# MasterCtrl_v1_0_4.net
KiCad netlist of a schematic drawn in EasyEDA Pro
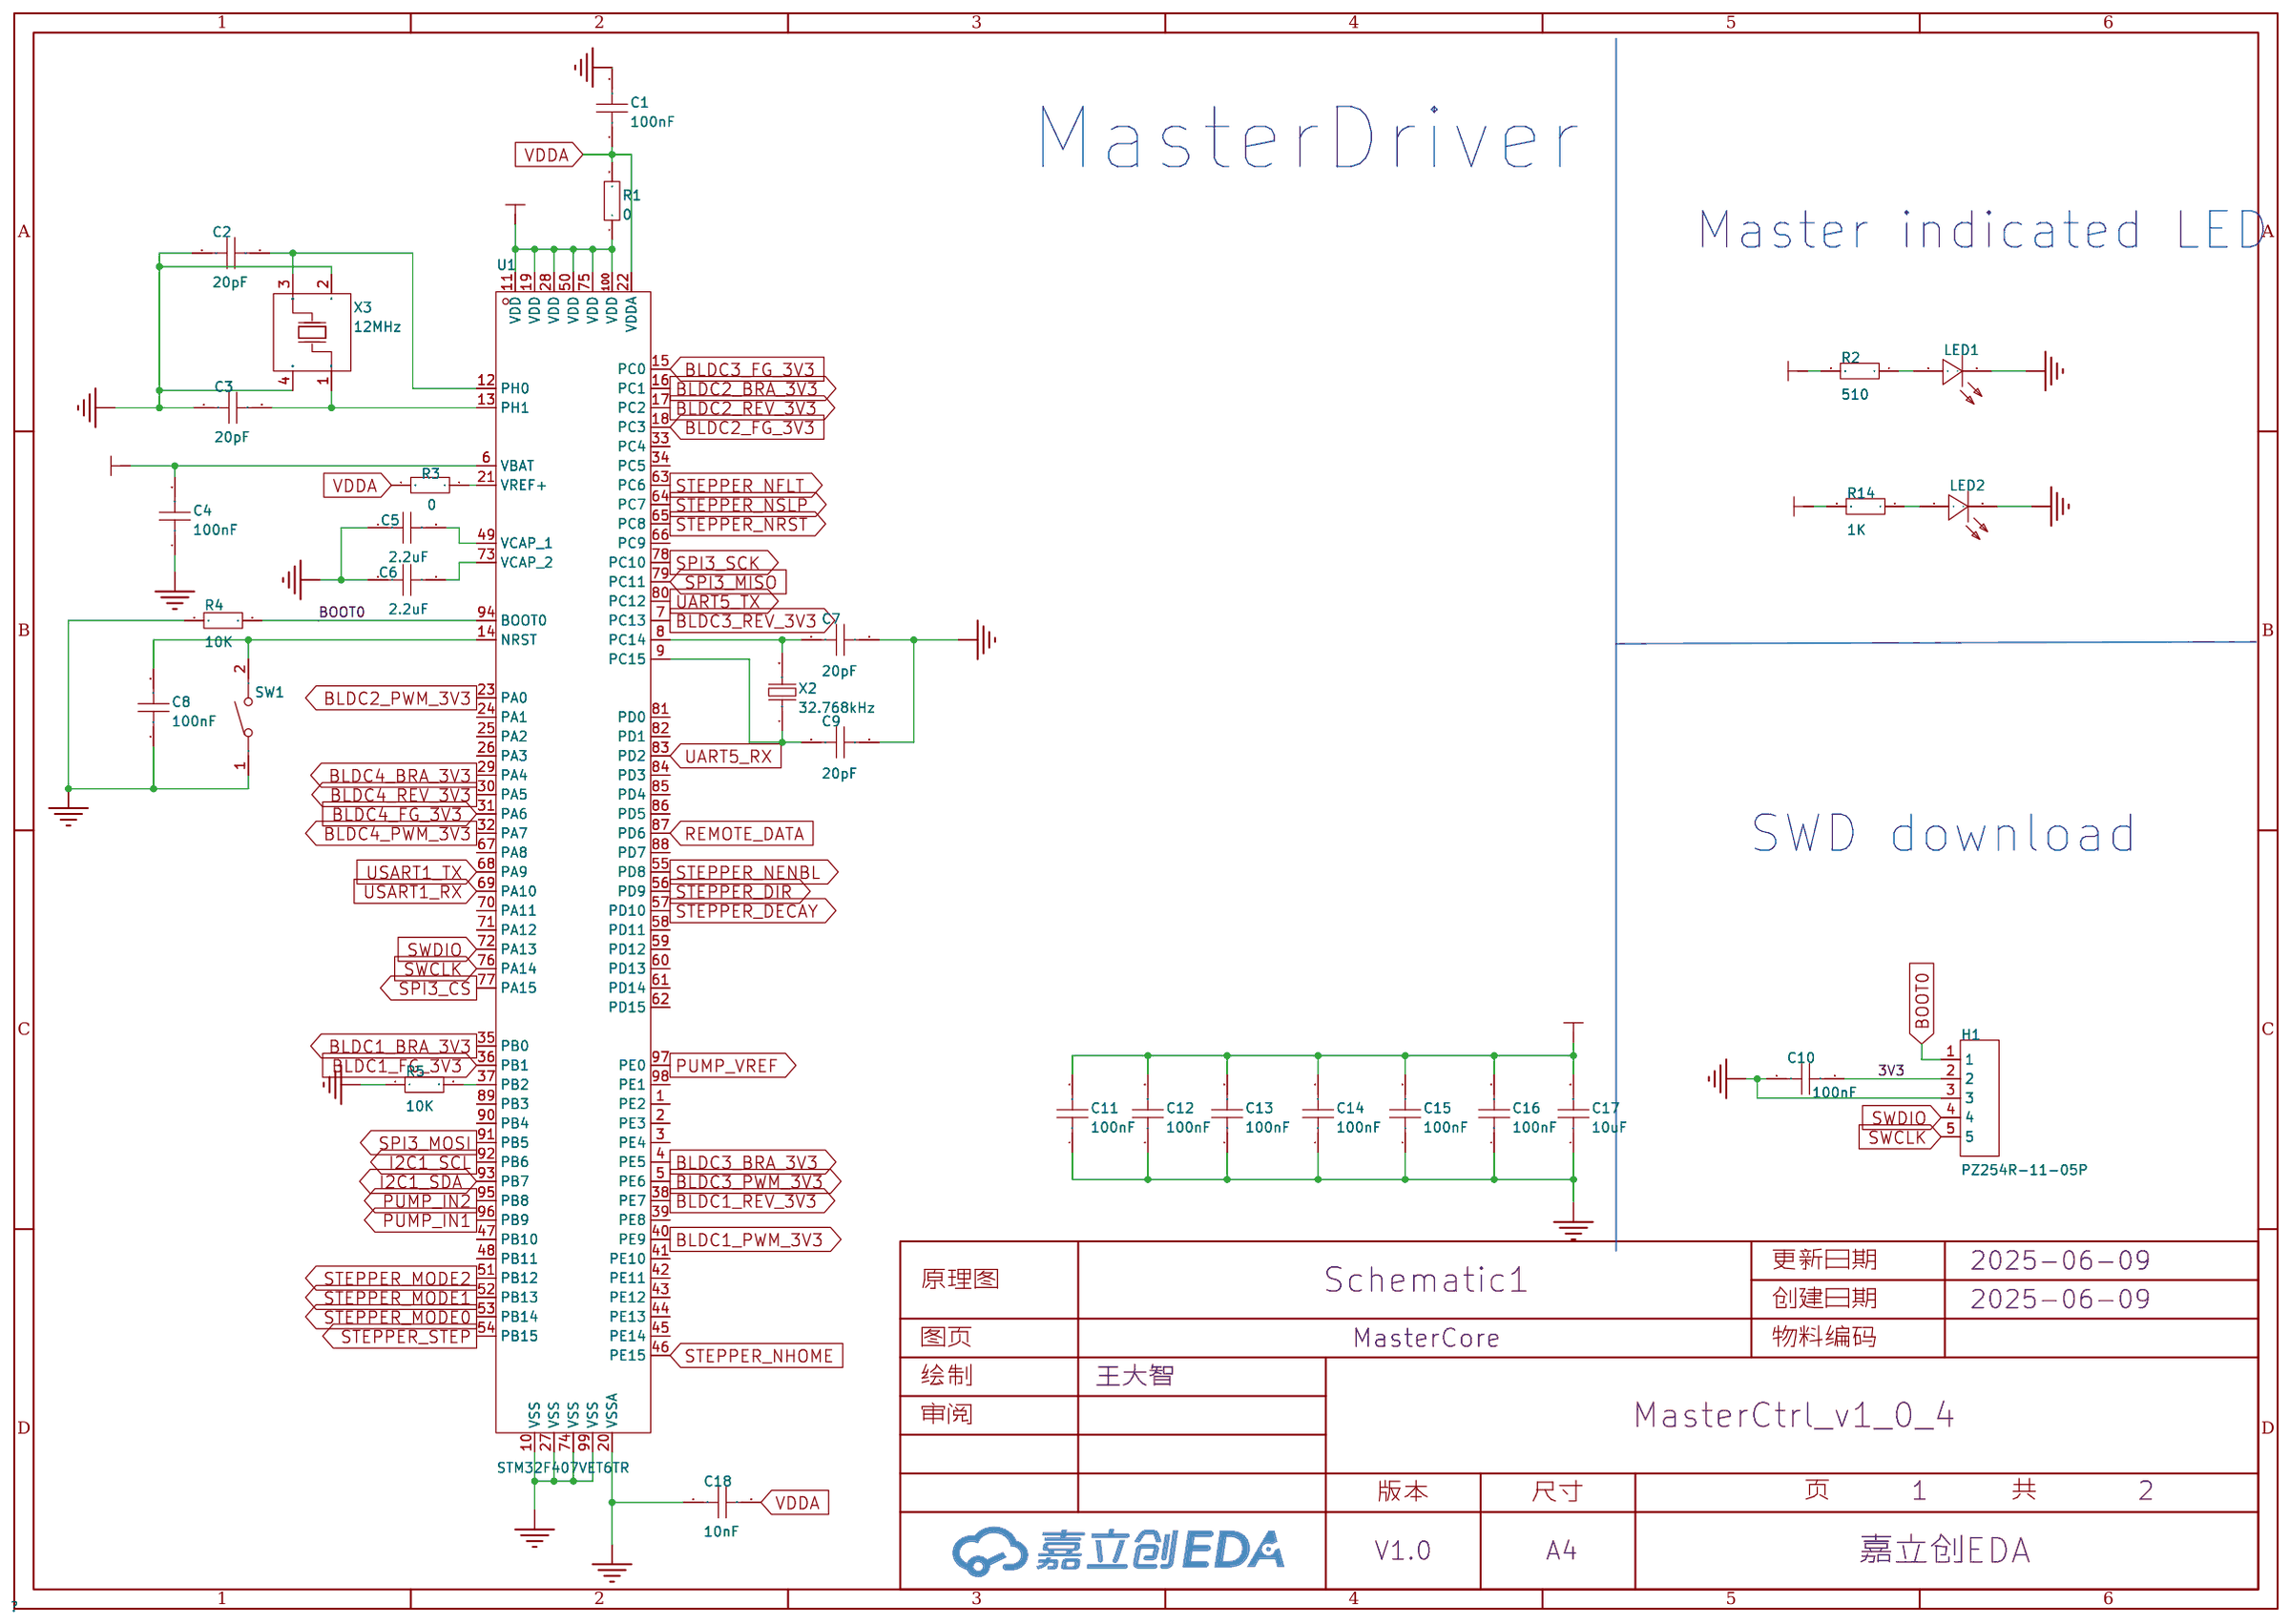
[diagram p0: MasterCore]
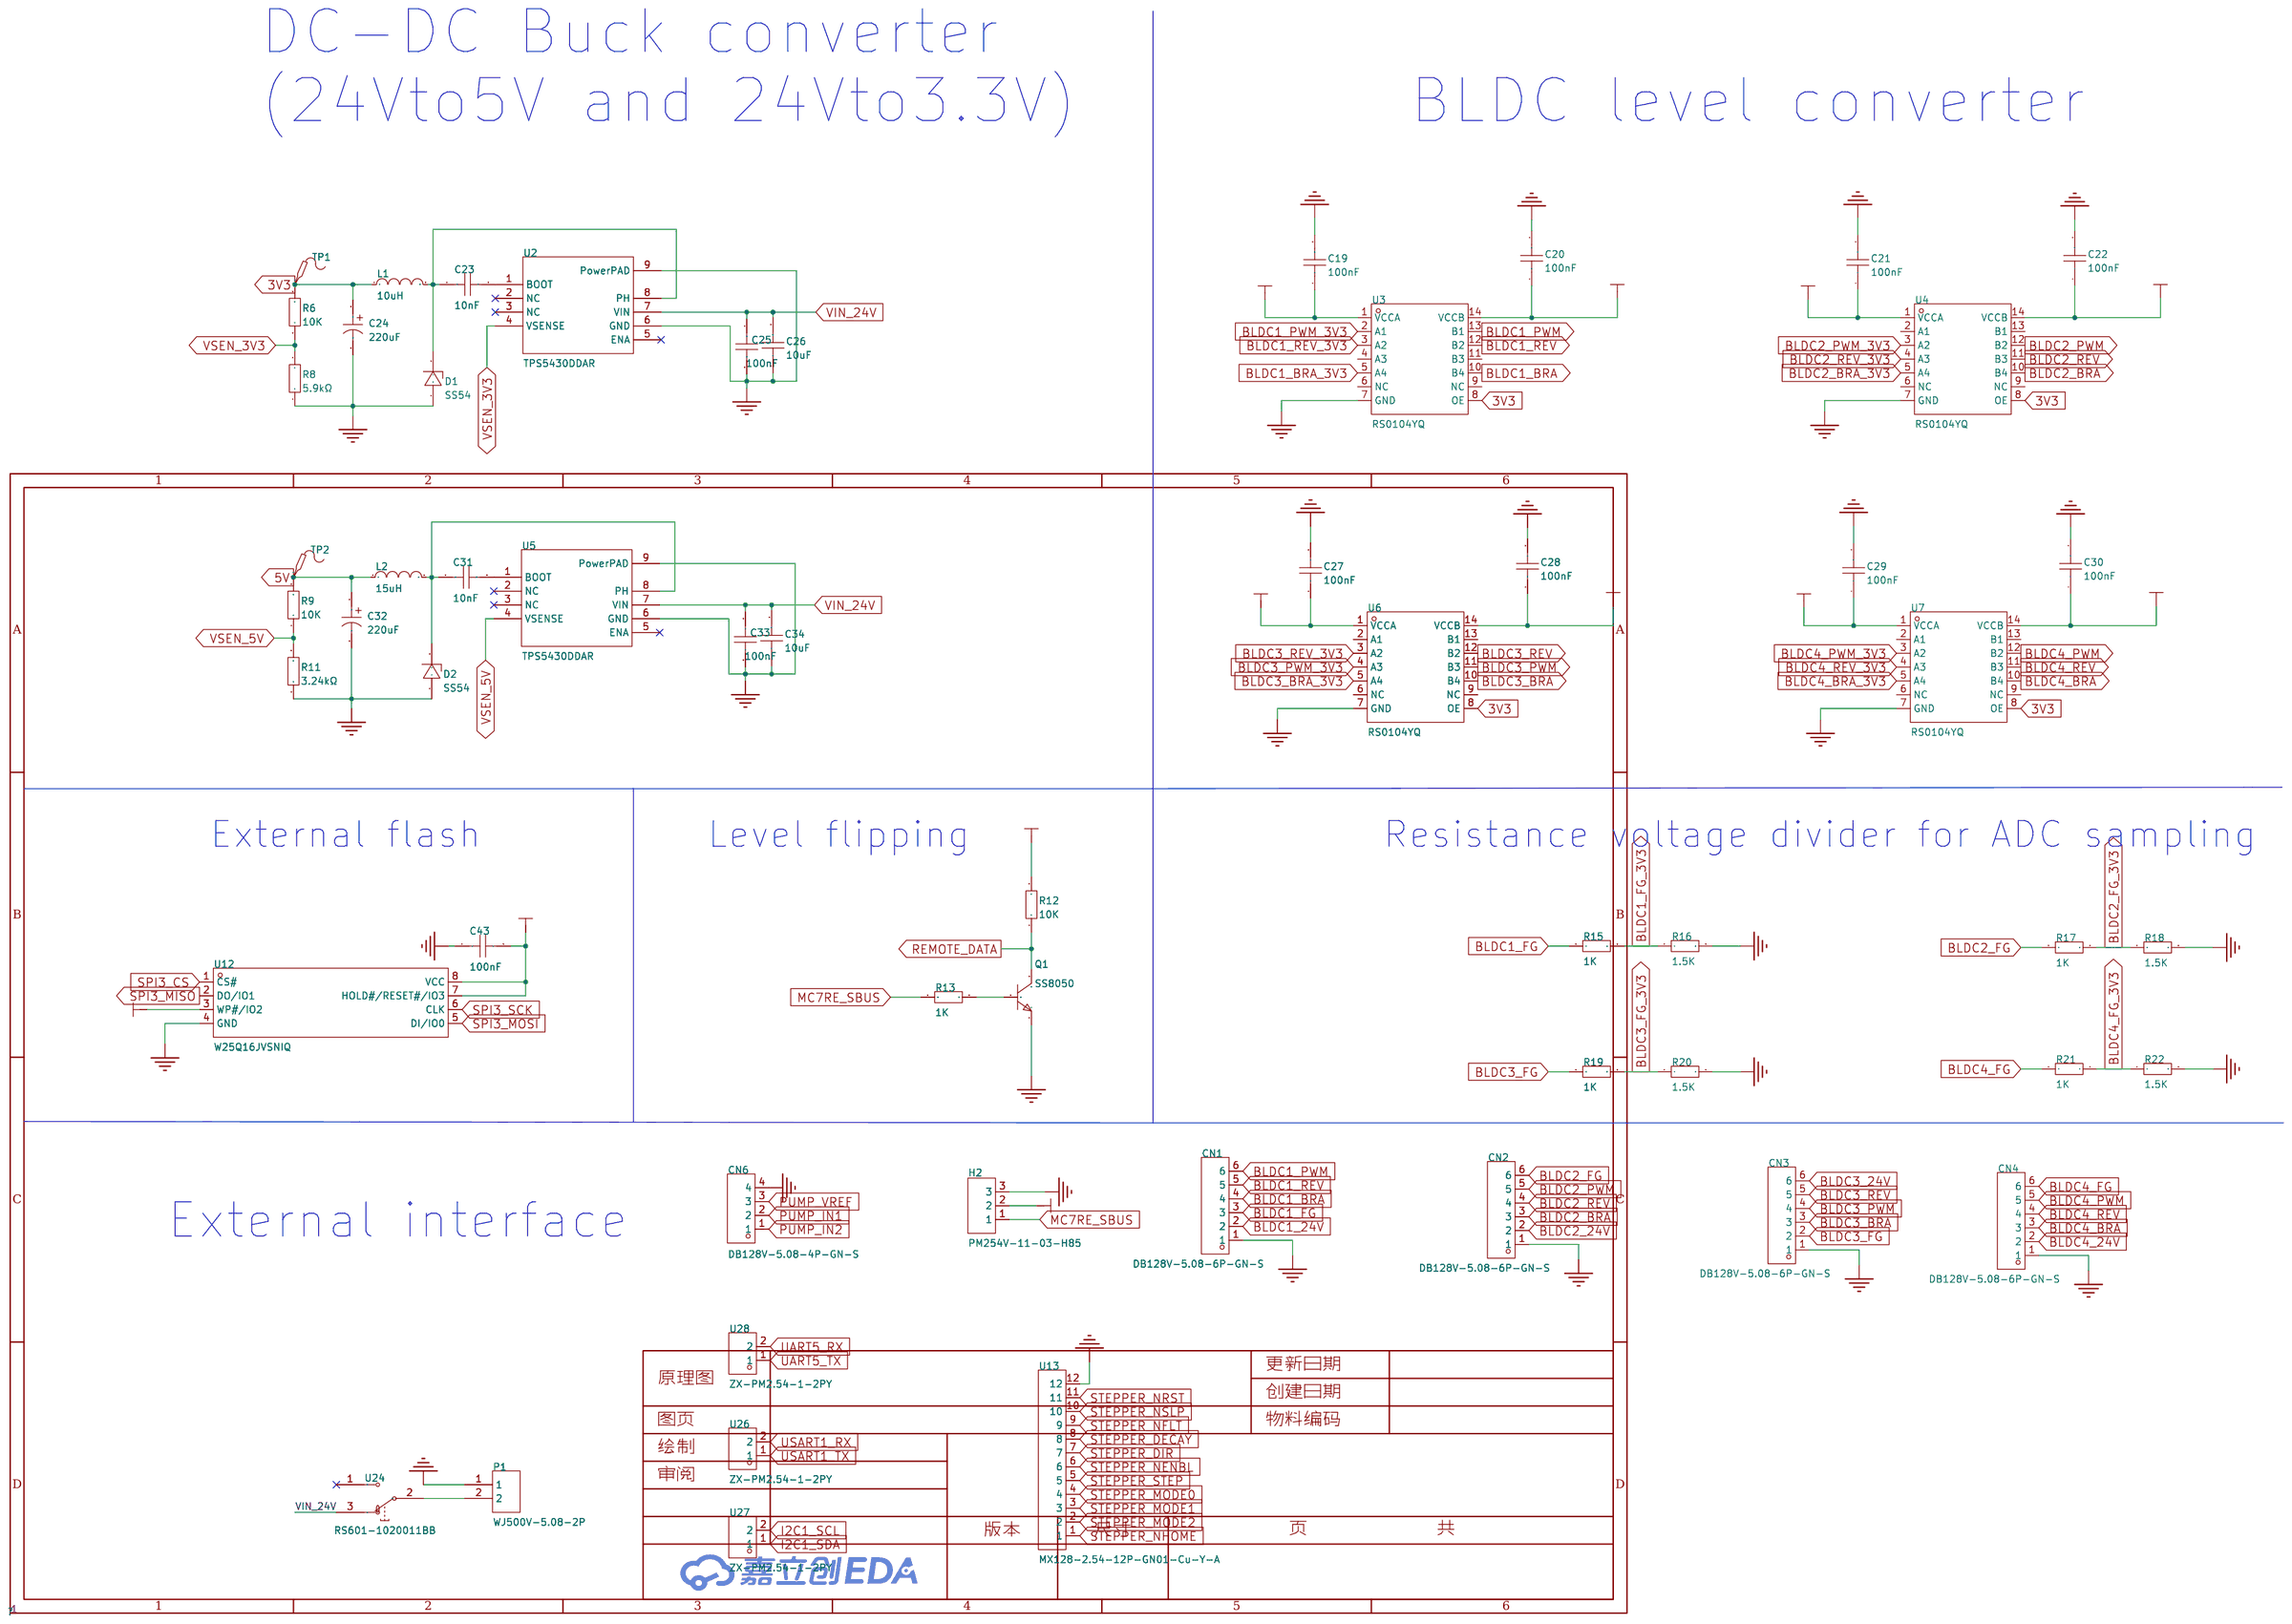
[diagram p1: ExternalCircuit]

(export (version "E")
  (design (tool "Eeschema 10.0.6"))
  (components
    (comp (ref "C1")
      (value "100nF")
      (footprint "easyedapro:C0603")
      (libsource (lib "easyedapro") (part "CapAcitance"))
    )
    (comp (ref "C2")
      (value "20pF")
      (footprint "easyedapro:C0603")
      (libsource (lib "easyedapro") (part "CapAcitance"))
    )
    (comp (ref "C3")
      (value "20pF")
      (footprint "easyedapro:C0603")
      (libsource (lib "easyedapro") (part "CapAcitance"))
    )
    (comp (ref "C4")
      (value "100nF")
      (footprint "easyedapro:C0603")
      (libsource (lib "easyedapro") (part "CapAcitance"))
    )
    (comp (ref "C5")
      (value "2.2uF")
      (footprint "easyedapro:C0603")
      (libsource (lib "easyedapro") (part "CapAcitance"))
    )
    (comp (ref "C6")
      (value "2.2uF")
      (footprint "easyedapro:C0603")
      (libsource (lib "easyedapro") (part "CapAcitance"))
    )
    (comp (ref "C7")
      (value "20pF")
      (footprint "easyedapro:C0603")
      (libsource (lib "easyedapro") (part "CapAcitance"))
    )
    (comp (ref "C8")
      (value "100nF")
      (footprint "easyedapro:C0603")
      (libsource (lib "easyedapro") (part "CapAcitance"))
    )
    (comp (ref "C9")
      (value "20pF")
      (footprint "easyedapro:C0603")
      (libsource (lib "easyedapro") (part "CapAcitance"))
    )
    (comp (ref "C10")
      (value "100nF")
      (footprint "easyedapro:C0603")
      (libsource (lib "easyedapro") (part "CapAcitance"))
    )
    (comp (ref "C11")
      (value "100nF")
      (footprint "easyedapro:C0603")
      (libsource (lib "easyedapro") (part "CapAcitance"))
    )
    (comp (ref "C12")
      (value "100nF")
      (footprint "easyedapro:C0603")
      (libsource (lib "easyedapro") (part "CapAcitance"))
    )
    (comp (ref "C13")
      (value "100nF")
      (footprint "easyedapro:C0603")
      (libsource (lib "easyedapro") (part "CapAcitance"))
    )
    (comp (ref "C14")
      (value "100nF")
      (footprint "easyedapro:C0603")
      (libsource (lib "easyedapro") (part "CapAcitance"))
    )
    (comp (ref "C15")
      (value "100nF")
      (footprint "easyedapro:C0603")
      (libsource (lib "easyedapro") (part "CapAcitance"))
    )
    (comp (ref "C16")
      (value "100nF")
      (footprint "easyedapro:C0603")
      (libsource (lib "easyedapro") (part "CapAcitance"))
    )
    (comp (ref "C17")
      (value "10uF")
      (footprint "easyedapro:C0603")
      (libsource (lib "easyedapro") (part "CapAcitance"))
    )
    (comp (ref "C18")
      (value "10nF")
      (footprint "easyedapro:C0603")
      (libsource (lib "easyedapro") (part "CapAcitance"))
    )
    (comp (ref "H1")
      (value "PZ254R-11-05P")
      (footprint "easyedapro:HDR-TH_5P-P2.54-H-M-W10.4")
      (fields (field (name "Manufacturer") "XFCN(兴飞)"))
      (libsource (lib "easyedapro") (part "PZ254R-11-05P"))
    )
    (comp (ref "LED1")
      (value "SZYY0805R")
      (footprint "easyedapro:LED0805-R-RD")
      (fields (field (name "Manufacturer") "yongyu(永裕光电)"))
      (libsource (lib "easyedapro") (part "SZYY0805R"))
    )
    (comp (ref "LED2")
      (value "SZYY0805R")
      (footprint "easyedapro:LED0805-R-RD")
      (fields (field (name "Manufacturer") "yongyu(永裕光电)"))
      (libsource (lib "easyedapro") (part "SZYY0805R"))
    )
    (comp (ref "R1") (value "0") (footprint "easyedapro:R0603") (libsource (lib "easyedapro") (part "电阻")))
    (comp (ref "R2") (value "510") (footprint "easyedapro:R0603") (libsource (lib "easyedapro") (part "电阻")))
    (comp (ref "R3") (value "0") (footprint "easyedapro:R0603") (libsource (lib "easyedapro") (part "电阻")))
    (comp (ref "R4") (value "10K") (footprint "easyedapro:R0603") (libsource (lib "easyedapro") (part "电阻")))
    (comp (ref "R5") (value "10K") (footprint "easyedapro:R0603") (libsource (lib "easyedapro") (part "电阻")))
    (comp (ref "R14") (value "1K") (footprint "easyedapro:R0603") (libsource (lib "easyedapro") (part "电阻")))
    (comp (ref "SW1")
      (value "TS-1088-AR02016")
      (footprint "easyedapro:SW-SMD_L3.9-W3.0-P4.45")
      (fields (field (name "Manufacturer") "XUNPU(讯普)"))
      (libsource (lib "easyedapro") (part "TS-1088-AR02016"))
    )
    (comp (ref "U1")
      (value "STM32F407VET6TR")
      (footprint "easyedapro:LQFP-100_L14.0-W14.0-P0.50-LS16.0-BL")
      (description "CPU内核:ARM-M4;CPU最大主频:168MHz;应用领域:-;")
      (fields (field (name "Manufacturer") "ST(意法半导体)"))
      (libsource (lib "easyedapro") (part "STM32F407VET6TR"))
    )
    (comp (ref "X2")
      (value "32.768kHz")
      (footprint "easyedapro:FC-135R_L3.2-W1.5")
      (description "晶振类型:贴片晶振;频率:32.768kHz;常温频差:±20ppm;负载电容:12.5pF;")
      (fields (field (name "Manufacturer Part") "Q13FC13500004") (field (name "Manufacturer") "EPSON(爱普生)"))
      (libsource (lib "easyedapro") (part "Q13FC1350000400"))
    )
    (comp (ref "X3")
      (value "12MHz")
      (footprint "easyedapro:CRYSTAL-SMD_4P-L3.2-W2.5-BL")
      (description "晶振类型:贴片晶振;频率:12MHz;常温频差:±10ppm;负载电容:20pF;频率稳定度:±20ppm;")
      (fields (field (name "Manufacturer Part") "X322512MSB4SI") (field (name "Manufacturer") "YXC(扬兴晶振)"))
      (libsource (lib "easyedapro") (part "X322512MSB4SI"))
    )
    (comp (ref "C19")
      (value "100nF")
      (footprint "easyedapro:C0603")
      (libsource (lib "easyedapro") (part "CapAcitance"))
    )
    (comp (ref "C20")
      (value "100nF")
      (footprint "easyedapro:C0603")
      (libsource (lib "easyedapro") (part "CapAcitance"))
    )
    (comp (ref "C21")
      (value "100nF")
      (footprint "easyedapro:C0603")
      (libsource (lib "easyedapro") (part "CapAcitance"))
    )
    (comp (ref "C22")
      (value "100nF")
      (footprint "easyedapro:C0603")
      (libsource (lib "easyedapro") (part "CapAcitance"))
    )
    (comp (ref "C23")
      (value "10nF")
      (footprint "easyedapro:C0603")
      (libsource (lib "easyedapro") (part "CapAcitance"))
    )
    (comp (ref "C24")
      (value "220uF")
      (footprint "easyedapro:CAP-SMD_BD8.0-L8.3-W8.3-FD")
      (description "容值:220uF;精度:±20%;额定电压:35V;纹波电流:175mA@120Hz;")
      (fields
        (field (name "Manufacturer Part") "GVT1V227M0810CNVC")
        (field (name "Manufacturer") "HRK(鸿瑞凯电子)")
      )
      (libsource (lib "easyedapro") (part "GVT1V227M0810CNVC"))
    )
    (comp (ref "C25")
      (value "100nF")
      (footprint "easyedapro:C0603")
      (libsource (lib "easyedapro") (part "CapAcitance"))
    )
    (comp (ref "C26")
      (value "10uF")
      (footprint "easyedapro:C1206")
      (description "容值:10uF;精度:±10%;额定电压:50V;温度系数:X5R;")
      (fields
        (field (name "Manufacturer Part") "HGC1206R5106K500NSPJ")
        (field (name "Manufacturer") "Chinocera(华瓷)")
      )
      (libsource (lib "easyedapro") (part "HGC1206R5106K500NSPJ"))
    )
    (comp (ref "C27")
      (value "100nF")
      (footprint "easyedapro:C0603")
      (libsource (lib "easyedapro") (part "CapAcitance"))
    )
    (comp (ref "C28")
      (value "100nF")
      (footprint "easyedapro:C0603")
      (libsource (lib "easyedapro") (part "CapAcitance"))
    )
    (comp (ref "C29")
      (value "100nF")
      (footprint "easyedapro:C0603")
      (libsource (lib "easyedapro") (part "CapAcitance"))
    )
    (comp (ref "C30")
      (value "100nF")
      (footprint "easyedapro:C0603")
      (libsource (lib "easyedapro") (part "CapAcitance"))
    )
    (comp (ref "C31")
      (value "10nF")
      (footprint "easyedapro:C0603")
      (libsource (lib "easyedapro") (part "CapAcitance"))
    )
    (comp (ref "C32")
      (value "220uF")
      (footprint "easyedapro:CAP-SMD_BD8.0-L8.3-W8.3-FD")
      (description "容值:220uF;精度:±20%;额定电压:35V;纹波电流:175mA@120Hz;")
      (fields
        (field (name "Manufacturer Part") "GVT1V227M0810CNVC")
        (field (name "Manufacturer") "HRK(鸿瑞凯电子)")
      )
      (libsource (lib "easyedapro") (part "GVT1V227M0810CNVC"))
    )
    (comp (ref "C33")
      (value "100nF")
      (footprint "easyedapro:C0603")
      (libsource (lib "easyedapro") (part "CapAcitance"))
    )
    (comp (ref "C34")
      (value "10uF")
      (footprint "easyedapro:C1206")
      (description "容值:10uF;精度:±10%;额定电压:50V;温度系数:X5R;")
      (fields
        (field (name "Manufacturer Part") "HGC1206R5106K500NSPJ")
        (field (name "Manufacturer") "Chinocera(华瓷)")
      )
      (libsource (lib "easyedapro") (part "HGC1206R5106K500NSPJ"))
    )
    (comp (ref "C43")
      (value "100nF")
      (footprint "easyedapro:C0603")
      (libsource (lib "easyedapro") (part "CapAcitance"))
    )
    (comp (ref "CN1")
      (value "DB128V-5.08-6P-GN-S")
      (footprint "easyedapro:CONN-TH_6P-P5.08_DIBO_DB128V-5.08")
      (fields (field (name "Manufacturer") "DORABO(地博电气)"))
      (libsource (lib "easyedapro") (part "DB128V-5.08-6P-GN-S"))
    )
    (comp (ref "CN2")
      (value "DB128V-5.08-6P-GN-S")
      (footprint "easyedapro:CONN-TH_6P-P5.08_DIBO_DB128V-5.08")
      (fields (field (name "Manufacturer") "DORABO(地博电气)"))
      (libsource (lib "easyedapro") (part "DB128V-5.08-6P-GN-S"))
    )
    (comp (ref "CN3")
      (value "DB128V-5.08-6P-GN-S")
      (footprint "easyedapro:CONN-TH_6P-P5.08_DIBO_DB128V-5.08")
      (fields (field (name "Manufacturer") "DORABO(地博电气)"))
      (libsource (lib "easyedapro") (part "DB128V-5.08-6P-GN-S"))
    )
    (comp (ref "CN4")
      (value "DB128V-5.08-6P-GN-S")
      (footprint "easyedapro:CONN-TH_6P-P5.08_DIBO_DB128V-5.08")
      (fields (field (name "Manufacturer") "DORABO(地博电气)"))
      (libsource (lib "easyedapro") (part "DB128V-5.08-6P-GN-S"))
    )
    (comp (ref "CN6")
      (value "DB128V-5.08-4P-GN-S")
      (footprint "easyedapro:CONN-TH_4P-P5.08_DIBO_DB128V-5.08")
      (fields (field (name "Manufacturer") "DORABO(地博电气)"))
      (libsource (lib "easyedapro") (part "DB128V-5.08-4P-GN-S"))
    )
    (comp (ref "D1")
      (value "SS54")
      (footprint "easyedapro:SMA_L4.3-W2.6-LS5.0-FD")
      (description "二极管配置:独立式;正向压降(Vf):550mV@5.0A;直流反向耐压(Vr):40V;整流电流:5A;")
      (fields (field (name "Manufacturer") "宏迦橙"))
      (libsource (lib "easyedapro") (part "SS54_C7420369"))
    )
    (comp (ref "D2")
      (value "SS54")
      (footprint "easyedapro:SMA_L4.3-W2.6-LS5.0-FD")
      (description "二极管配置:独立式;正向压降(Vf):550mV@5.0A;直流反向耐压(Vr):40V;整流电流:5A;")
      (fields (field (name "Manufacturer") "宏迦橙"))
      (libsource (lib "easyedapro") (part "SS54_C7420369"))
    )
    (comp (ref "H2")
      (value "PM254V-11-03-H85")
      (footprint "easyedapro:HDR-TH_3P-P2.54-V-F")
      (description "插孔结构:1x3P;间距:2.54mm;行距:-;安装类型:直插;排数:单排;总孔位数:3P;塑高:-;触头材质:黄铜;触头镀层:-;")
      (fields (field (name "Manufacturer") "XFCN(兴飞)"))
      (libsource (lib "easyedapro") (part "PM254V-11-03-H85"))
    )
    (comp (ref "L1")
      (value "10uH")
      (footprint "easyedapro:IND-SMD_L7.3-W6.8")
      (description "电感值:10uH;精度:±20%;额定电流:4.5A;饱和电流(Isat):5.5A;类型:一体成型电感;")
      (fields (field (name "Manufacturer Part") "FXL0630-100-M") (field (name "Manufacturer") "cjiang(长江微电)"))
      (libsource (lib "easyedapro") (part "FXL0630-100-M"))
    )
    (comp (ref "L2")
      (value "15uH")
      (footprint "easyedapro:IND-SMD_L7.0-W6.6_FXL0630")
      (description "电感值:15uH;精度:±20%;额定电流:3A;饱和电流(Isat):4.5A;类型:一体成型电感;")
      (fields (field (name "Manufacturer Part") "FXL0630-150-M") (field (name "Manufacturer") "cjiang(长江微电)"))
      (libsource (lib "easyedapro") (part "FXL0630-150-M"))
    )
    (comp (ref "P1")
      (value "WJ500V-5.08-2P")
      (footprint "easyedapro:CONN-TH_2P-P5.00_WJ500V-5.08-2P")
      (fields (field (name "Manufacturer") "KANGNEX(康奈克斯电气)"))
      (libsource (lib "easyedapro") (part "WJ500V-5.08-2P-14-00A"))
    )
    (comp (ref "Q1")
      (value "SS8050")
      (footprint "easyedapro:SOT-23-3_L2.9-W1.3-P1.90-LS2.4-BR")
      (description "晶体管类型:NPN;集电极电流(Ic):1.5A;集射极击穿电压(Vceo):25V;耗散功率(Pd):300mW;直流电流增益(hFE):120@100mA,1.0V;")
      (fields (field (name "Manufacturer") "宏嘉诚"))
      (libsource (lib "easyedapro") (part "SS8050_C7420370"))
    )
    (comp (ref "R6") (value "10K") (footprint "easyedapro:R0603") (libsource (lib "easyedapro") (part "电阻")))
    (comp (ref "R8")
      (value "5.9kΩ")
      (footprint "easyedapro:R0603")
      (description "电阻类型:厚膜电阻;阻值:5.9kΩ;精度:±1%;功率:100mW;最大工作电压:75V;温度系数:±100ppm/°C;")
      (fields
        (field (name "Manufacturer Part") "0603WAF5901T5E")
        (field (name "Manufacturer") "UNI-ROYAL(厚声)")
      )
      (libsource (lib "easyedapro") (part "0603WAF5901T5E"))
    )
    (comp (ref "R9") (value "10K") (footprint "easyedapro:R0603") (libsource (lib "easyedapro") (part "电阻")))
    (comp (ref "R11")
      (value "3.24kΩ")
      (footprint "easyedapro:R0603")
      (description "电阻类型:厚膜电阻;阻值:3.24kΩ;精度:±1%;功率:100mW;最大工作电压:75V;温度系数:±100ppm/°C;")
      (fields
        (field (name "Manufacturer Part") "0603WAF3241T5E")
        (field (name "Manufacturer") "UNI-ROYAL(厚声)")
      )
      (libsource (lib "easyedapro") (part "0603WAF3241T5E"))
    )
    (comp (ref "R12") (value "10K") (footprint "easyedapro:R0603") (libsource (lib "easyedapro") (part "电阻")))
    (comp (ref "R13") (value "1K") (footprint "easyedapro:R0603") (libsource (lib "easyedapro") (part "电阻")))
    (comp (ref "R15") (value "1K") (footprint "easyedapro:R0603") (libsource (lib "easyedapro") (part "电阻")))
    (comp (ref "R16")
      (value "1.5K")
      (footprint "easyedapro:R0603")
      (libsource (lib "easyedapro") (part "电阻"))
    )
    (comp (ref "R17") (value "1K") (footprint "easyedapro:R0603") (libsource (lib "easyedapro") (part "电阻")))
    (comp (ref "R18")
      (value "1.5K")
      (footprint "easyedapro:R0603")
      (libsource (lib "easyedapro") (part "电阻"))
    )
    (comp (ref "R19") (value "1K") (footprint "easyedapro:R0603") (libsource (lib "easyedapro") (part "电阻")))
    (comp (ref "R20")
      (value "1.5K")
      (footprint "easyedapro:R0603")
      (libsource (lib "easyedapro") (part "电阻"))
    )
    (comp (ref "R21") (value "1K") (footprint "easyedapro:R0603") (libsource (lib "easyedapro") (part "电阻")))
    (comp (ref "R22")
      (value "1.5K")
      (footprint "easyedapro:R0603")
      (libsource (lib "easyedapro") (part "电阻"))
    )
    (comp (ref "TP1")
      (value "~")
      (footprint "easyedapro:Test-Point-0.5mm")
      (description "Test Point 测试点")
      (libsource (lib "easyedapro") (part "Test-Point"))
    )
    (comp (ref "TP2")
      (value "~")
      (footprint "easyedapro:Test-Point-0.5mm")
      (description "Test Point 测试点")
      (libsource (lib "easyedapro") (part "Test-Point"))
    )
    (comp (ref "U2")
      (value "TPS5430DDAR")
      (footprint "easyedapro:ESOP-8_L4.9-W3.9-P1.27-LS6.0-TL-EP")
      (description "功能类型:降压型;输出类型:可调;工作电压:5.5V~36V;输出电压:1.221V~32.04V;输出电流:3A;")
      (fields (field (name "Manufacturer") "TI(德州仪器)"))
      (libsource (lib "easyedapro") (part "TPS5430DDAR"))
    )
    (comp (ref "U3")
      (value "RS0104YQ")
      (footprint "easyedapro:TSSOP-14_L5.0-W4.4-P0.65-LS6.4-BL")
      (description "数据速率:24Mbps;电压(VCCA):1.65V~5.5V;电压(VCCB):2.3V~5.5V;电路数:1;每个电路通道数:4;")
      (fields (field (name "Manufacturer") "RUNIC(润石)"))
      (libsource (lib "easyedapro") (part "RS0104YQ"))
    )
    (comp (ref "U4")
      (value "RS0104YQ")
      (footprint "easyedapro:TSSOP-14_L5.0-W4.4-P0.65-LS6.4-BL")
      (description "数据速率:24Mbps;电压(VCCA):1.65V~5.5V;电压(VCCB):2.3V~5.5V;电路数:1;每个电路通道数:4;")
      (fields (field (name "Manufacturer") "RUNIC(润石)"))
      (libsource (lib "easyedapro") (part "RS0104YQ"))
    )
    (comp (ref "U5")
      (value "TPS5430DDAR")
      (footprint "easyedapro:ESOP-8_L4.9-W3.9-P1.27-LS6.0-TL-EP")
      (description "功能类型:降压型;输出类型:可调;工作电压:5.5V~36V;输出电压:1.221V~32.04V;输出电流:3A;")
      (fields (field (name "Manufacturer") "TI(德州仪器)"))
      (libsource (lib "easyedapro") (part "TPS5430DDAR"))
    )
    (comp (ref "U6")
      (value "RS0104YQ")
      (footprint "easyedapro:TSSOP-14_L5.0-W4.4-P0.65-LS6.4-BL")
      (description "数据速率:24Mbps;电压(VCCA):1.65V~5.5V;电压(VCCB):2.3V~5.5V;电路数:1;每个电路通道数:4;")
      (fields (field (name "Manufacturer") "RUNIC(润石)"))
      (libsource (lib "easyedapro") (part "RS0104YQ"))
    )
    (comp (ref "U7")
      (value "RS0104YQ")
      (footprint "easyedapro:TSSOP-14_L5.0-W4.4-P0.65-LS6.4-BL")
      (description "数据速率:24Mbps;电压(VCCA):1.65V~5.5V;电压(VCCB):2.3V~5.5V;电路数:1;每个电路通道数:4;")
      (fields (field (name "Manufacturer") "RUNIC(润石)"))
      (libsource (lib "easyedapro") (part "RS0104YQ"))
    )
    (comp (ref "U12")
      (value "W25Q16JVSNIQ")
      (footprint "easyedapro:SOP-8_L4.9-W3.9-P1.27-LS6.0-BL")
      (fields (field (name "Manufacturer") "WINBOND(华邦)"))
      (libsource (lib "easyedapro") (part "W25Q16JVSNIQ TR"))
    )
    (comp (ref "U13")
      (value "MX128-2.54-12P-GN01-Cu-Y-A")
      (footprint "easyedapro:CONN-TH_12P-P2.54_MX128-2.54-12P-GN01-CU-Y-A")
      (fields (field (name "Manufacturer") "MAX(迈旭)"))
      (libsource (lib "easyedapro") (part "MX128-2.54-12P-GN01-CU-Y-A"))
    )
    (comp (ref "U24")
      (value "RS601-1020011BB")
      (footprint "easyedapro:SW-TH_RS601-1020011BB")
      (description "带灯:无;引脚样式:焊片;额定电流:8A;额定电压(AC):250V;额定电压(DC):-;电路结构:单刀双掷;机械寿命:1万次;")
      (fields (field (name "Manufacturer") "HCTL(华灿天禄)"))
      (libsource (lib "easyedapro") (part "RS601-1020011BB"))
    )
    (comp (ref "U26")
      (value "ZX-PM2.54-1-2PY")
      (footprint "easyedapro:HDR-TH_2P-P2.54-V-F")
      (fields (field (name "Manufacturer") "Megastar(兆星)"))
      (libsource (lib "easyedapro") (part "ZX-PM2.54-1-2PY"))
    )
    (comp (ref "U27")
      (value "ZX-PM2.54-1-2PY")
      (footprint "easyedapro:HDR-TH_2P-P2.54-V-F")
      (fields (field (name "Manufacturer") "Megastar(兆星)"))
      (libsource (lib "easyedapro") (part "ZX-PM2.54-1-2PY"))
    )
    (comp (ref "U28")
      (value "ZX-PM2.54-1-2PY")
      (footprint "easyedapro:HDR-TH_2P-P2.54-V-F")
      (fields (field (name "Manufacturer") "Megastar(兆星)"))
      (libsource (lib "easyedapro") (part "ZX-PM2.54-1-2PY"))
    )
  )
  (nets
    (net (code "1") (name "3V3") (class "Default")
      (node (ref "C10") (pin "2") (pinfunction "2_2") (pintype "input"))
      (node (ref "C11") (pin "2") (pinfunction "2_2") (pintype "input"))
      (node (ref "C12") (pin "2") (pinfunction "2_2") (pintype "input"))
      (node (ref "C13") (pin "2") (pinfunction "2_2") (pintype "input"))
      (node (ref "C14") (pin "2") (pinfunction "2_2") (pintype "input"))
      (node (ref "C15") (pin "2") (pinfunction "2_2") (pintype "input"))
      (node (ref "C16") (pin "2") (pinfunction "2_2") (pintype "input"))
      (node (ref "C17") (pin "2") (pinfunction "2_2") (pintype "input"))
      (node (ref "C19") (pin "1") (pinfunction "1_1") (pintype "input"))
      (node (ref "C21") (pin "1") (pinfunction "1_1") (pintype "input"))
      (node (ref "C24") (pin "1") (pinfunction "1_1") (pintype "input"))
      (node (ref "C27") (pin "1") (pinfunction "1_1") (pintype "input"))
      (node (ref "C29") (pin "1") (pinfunction "1_1") (pintype "input"))
      (node (ref "C4") (pin "2") (pinfunction "2_2") (pintype "input"))
      (node (ref "C43") (pin "2") (pinfunction "2_2") (pintype "input"))
      (node (ref "H1") (pin "2") (pinfunction "2_2") (pintype "unspecified"))
      (node (ref "L1") (pin "1") (pinfunction "1_1") (pintype "unspecified"))
      (node (ref "R1") (pin "1") (pinfunction "1_1") (pintype "input"))
      (node (ref "R12") (pin "2") (pinfunction "2_2") (pintype "input"))
      (node (ref "R2") (pin "2") (pinfunction "2_2") (pintype "input"))
      (node (ref "R6") (pin "2") (pinfunction "2_2") (pintype "input"))
      (node (ref "TP1") (pin "1") (pinfunction "1_1") (pintype "input"))
      (node (ref "U1") (pin "100") (pinfunction "VDD_100") (pintype "unspecified"))
      (node (ref "U1") (pin "11") (pinfunction "VDD_11") (pintype "unspecified"))
      (node (ref "U1") (pin "19") (pinfunction "VDD_19") (pintype "unspecified"))
      (node (ref "U1") (pin "28") (pinfunction "VDD_28") (pintype "unspecified"))
      (node (ref "U1") (pin "50") (pinfunction "VDD_50") (pintype "unspecified"))
      (node (ref "U1") (pin "6") (pinfunction "VBAT_6") (pintype "unspecified"))
      (node (ref "U1") (pin "75") (pinfunction "VDD_75") (pintype "unspecified"))
      (node (ref "U12") (pin "3") (pinfunction "WP#/IO2_3") (pintype "unspecified"))
      (node (ref "U12") (pin "7") (pinfunction "HOLD#/RESET#/IO3_7") (pintype "unspecified"))
      (node (ref "U12") (pin "8") (pinfunction "VCC_8") (pintype "unspecified"))
      (node (ref "U3") (pin "1") (pinfunction "VCCA_1") (pintype "unspecified"))
      (node (ref "U3") (pin "8") (pinfunction "OE_8") (pintype "unspecified"))
      (node (ref "U4") (pin "1") (pinfunction "VCCA_1") (pintype "unspecified"))
      (node (ref "U4") (pin "8") (pinfunction "OE_8") (pintype "unspecified"))
      (node (ref "U6") (pin "1") (pinfunction "VCCA_1") (pintype "unspecified"))
      (node (ref "U6") (pin "8") (pinfunction "OE_8") (pintype "unspecified"))
      (node (ref "U7") (pin "1") (pinfunction "VCCA_1") (pintype "unspecified"))
      (node (ref "U7") (pin "8") (pinfunction "OE_8") (pintype "unspecified"))
    )
    (net (code "2") (name "5V") (class "Default")
      (node (ref "C20") (pin "1") (pinfunction "1_1") (pintype "input"))
      (node (ref "C22") (pin "1") (pinfunction "1_1") (pintype "input"))
      (node (ref "C28") (pin "1") (pinfunction "1_1") (pintype "input"))
      (node (ref "C30") (pin "1") (pinfunction "1_1") (pintype "input"))
      (node (ref "C32") (pin "1") (pinfunction "1_1") (pintype "input"))
      (node (ref "H2") (pin "2") (pinfunction "2_2") (pintype "unspecified"))
      (node (ref "L2") (pin "1") (pinfunction "1_1") (pintype "unspecified"))
      (node (ref "R14") (pin "2") (pinfunction "2_2") (pintype "input"))
      (node (ref "R9") (pin "2") (pinfunction "2_2") (pintype "input"))
      (node (ref "TP2") (pin "1") (pinfunction "1_1") (pintype "input"))
      (node (ref "U3") (pin "14") (pinfunction "VCCB_14") (pintype "unspecified"))
      (node (ref "U4") (pin "14") (pinfunction "VCCB_14") (pintype "unspecified"))
      (node (ref "U6") (pin "14") (pinfunction "VCCB_14") (pintype "unspecified"))
      (node (ref "U7") (pin "14") (pinfunction "VCCB_14") (pintype "unspecified"))
    )
    (net (code "3") (name "BLDC1_24V") (class "Default")
      (node (ref "CN1") (pin "2") (pinfunction "2_2") (pintype "unspecified"))
    )
    (net (code "4") (name "BLDC1_BRA") (class "Default")
      (node (ref "CN1") (pin "4") (pinfunction "4_4") (pintype "unspecified"))
      (node (ref "U3") (pin "10") (pinfunction "B4_10") (pintype "unspecified"))
    )
    (net (code "5") (name "BLDC1_BRA_3V3") (class "Default")
      (node (ref "U1") (pin "35") (pinfunction "PB0_35") (pintype "unspecified"))
      (node (ref "U3") (pin "5") (pinfunction "A4_5") (pintype "unspecified"))
    )
    (net (code "6") (name "BLDC1_FG") (class "Default")
      (node (ref "CN1") (pin "3") (pinfunction "3_3") (pintype "unspecified"))
      (node (ref "R15") (pin "1") (pinfunction "1_1") (pintype "input"))
    )
    (net (code "7") (name "BLDC1_FG_3V3") (class "Default")
      (node (ref "R15") (pin "2") (pinfunction "2_2") (pintype "input"))
      (node (ref "R16") (pin "1") (pinfunction "1_1") (pintype "input"))
      (node (ref "U1") (pin "36") (pinfunction "PB1_36") (pintype "unspecified"))
    )
    (net (code "8") (name "BLDC1_PWM") (class "Default")
      (node (ref "CN1") (pin "6") (pinfunction "6_6") (pintype "unspecified"))
      (node (ref "U3") (pin "13") (pinfunction "B1_13") (pintype "unspecified"))
    )
    (net (code "9") (name "BLDC1_PWM_3V3") (class "Default")
      (node (ref "U1") (pin "40") (pinfunction "PE9_40") (pintype "unspecified"))
      (node (ref "U3") (pin "2") (pinfunction "A1_2") (pintype "unspecified"))
    )
    (net (code "10") (name "BLDC1_REV") (class "Default")
      (node (ref "CN1") (pin "5") (pinfunction "5_5") (pintype "unspecified"))
      (node (ref "U3") (pin "12") (pinfunction "B2_12") (pintype "unspecified"))
    )
    (net (code "11") (name "BLDC1_REV_3V3") (class "Default")
      (node (ref "U1") (pin "38") (pinfunction "PE7_38") (pintype "unspecified"))
      (node (ref "U3") (pin "3") (pinfunction "A2_3") (pintype "unspecified"))
    )
    (net (code "12") (name "BLDC2_24V") (class "Default")
      (node (ref "CN2") (pin "2") (pinfunction "2_2") (pintype "unspecified"))
    )
    (net (code "13") (name "BLDC2_BRA") (class "Default")
      (node (ref "CN2") (pin "3") (pinfunction "3_3") (pintype "unspecified"))
      (node (ref "U4") (pin "10") (pinfunction "B4_10") (pintype "unspecified"))
    )
    (net (code "14") (name "BLDC2_BRA_3V3") (class "Default")
      (node (ref "U1") (pin "16") (pinfunction "PC1_16") (pintype "unspecified"))
      (node (ref "U4") (pin "5") (pinfunction "A4_5") (pintype "unspecified"))
    )
    (net (code "15") (name "BLDC2_FG") (class "Default")
      (node (ref "CN2") (pin "6") (pinfunction "6_6") (pintype "unspecified"))
      (node (ref "R17") (pin "1") (pinfunction "1_1") (pintype "input"))
    )
    (net (code "16") (name "BLDC2_FG_3V3") (class "Default")
      (node (ref "R17") (pin "2") (pinfunction "2_2") (pintype "input"))
      (node (ref "R18") (pin "1") (pinfunction "1_1") (pintype "input"))
      (node (ref "U1") (pin "18") (pinfunction "PC3_18") (pintype "unspecified"))
    )
    (net (code "17") (name "BLDC2_PWM") (class "Default")
      (node (ref "CN2") (pin "5") (pinfunction "5_5") (pintype "unspecified"))
      (node (ref "U4") (pin "12") (pinfunction "B2_12") (pintype "unspecified"))
    )
    (net (code "18") (name "BLDC2_PWM_3V3") (class "Default")
      (node (ref "U1") (pin "23") (pinfunction "PA0_23") (pintype "unspecified"))
      (node (ref "U4") (pin "3") (pinfunction "A2_3") (pintype "unspecified"))
    )
    (net (code "19") (name "BLDC2_REV") (class "Default")
      (node (ref "CN2") (pin "4") (pinfunction "4_4") (pintype "unspecified"))
      (node (ref "U4") (pin "11") (pinfunction "B3_11") (pintype "unspecified"))
    )
    (net (code "20") (name "BLDC2_REV_3V3") (class "Default")
      (node (ref "U1") (pin "17") (pinfunction "PC2_17") (pintype "unspecified"))
      (node (ref "U4") (pin "4") (pinfunction "A3_4") (pintype "unspecified"))
    )
    (net (code "21") (name "BLDC3_24V") (class "Default")
      (node (ref "CN3") (pin "6") (pinfunction "6_6") (pintype "unspecified"))
    )
    (net (code "22") (name "BLDC3_BRA") (class "Default")
      (node (ref "CN3") (pin "3") (pinfunction "3_3") (pintype "unspecified"))
      (node (ref "U6") (pin "10") (pinfunction "B4_10") (pintype "unspecified"))
    )
    (net (code "23") (name "BLDC3_BRA_3V3") (class "Default")
      (node (ref "U1") (pin "4") (pinfunction "PE5_4") (pintype "unspecified"))
      (node (ref "U6") (pin "5") (pinfunction "A4_5") (pintype "unspecified"))
    )
    (net (code "24") (name "BLDC3_FG") (class "Default")
      (node (ref "CN3") (pin "2") (pinfunction "2_2") (pintype "unspecified"))
      (node (ref "R19") (pin "1") (pinfunction "1_1") (pintype "input"))
    )
    (net (code "25") (name "BLDC3_FG_3V3") (class "Default")
      (node (ref "R19") (pin "2") (pinfunction "2_2") (pintype "input"))
      (node (ref "R20") (pin "1") (pinfunction "1_1") (pintype "input"))
      (node (ref "U1") (pin "15") (pinfunction "PC0_15") (pintype "unspecified"))
    )
    (net (code "26") (name "BLDC3_PWM") (class "Default")
      (node (ref "CN3") (pin "4") (pinfunction "4_4") (pintype "unspecified"))
      (node (ref "U6") (pin "11") (pinfunction "B3_11") (pintype "unspecified"))
    )
    (net (code "27") (name "BLDC3_PWM_3V3") (class "Default")
      (node (ref "U1") (pin "5") (pinfunction "PE6_5") (pintype "unspecified"))
      (node (ref "U6") (pin "4") (pinfunction "A3_4") (pintype "unspecified"))
    )
    (net (code "28") (name "BLDC3_REV") (class "Default")
      (node (ref "CN3") (pin "5") (pinfunction "5_5") (pintype "unspecified"))
      (node (ref "U6") (pin "12") (pinfunction "B2_12") (pintype "unspecified"))
    )
    (net (code "29") (name "BLDC3_REV_3V3") (class "Default")
      (node (ref "U1") (pin "7") (pinfunction "PC13_7") (pintype "unspecified"))
      (node (ref "U6") (pin "3") (pinfunction "A2_3") (pintype "unspecified"))
    )
    (net (code "30") (name "BLDC4_24V") (class "Default")
      (node (ref "CN4") (pin "2") (pinfunction "2_2") (pintype "unspecified"))
    )
    (net (code "31") (name "BLDC4_BRA") (class "Default")
      (node (ref "CN4") (pin "3") (pinfunction "3_3") (pintype "unspecified"))
      (node (ref "U7") (pin "10") (pinfunction "B4_10") (pintype "unspecified"))
    )
    (net (code "32") (name "BLDC4_BRA_3V3") (class "Default")
      (node (ref "U1") (pin "29") (pinfunction "PA4_29") (pintype "unspecified"))
      (node (ref "U7") (pin "5") (pinfunction "A4_5") (pintype "unspecified"))
    )
    (net (code "33") (name "BLDC4_FG") (class "Default")
      (node (ref "CN4") (pin "6") (pinfunction "6_6") (pintype "unspecified"))
      (node (ref "R21") (pin "1") (pinfunction "1_1") (pintype "input"))
    )
    (net (code "34") (name "BLDC4_FG_3V3") (class "Default")
      (node (ref "R21") (pin "2") (pinfunction "2_2") (pintype "input"))
      (node (ref "R22") (pin "1") (pinfunction "1_1") (pintype "input"))
      (node (ref "U1") (pin "31") (pinfunction "PA6_31") (pintype "unspecified"))
    )
    (net (code "35") (name "BLDC4_PWM") (class "Default")
      (node (ref "CN4") (pin "5") (pinfunction "5_5") (pintype "unspecified"))
      (node (ref "U7") (pin "12") (pinfunction "B2_12") (pintype "unspecified"))
    )
    (net (code "36") (name "BLDC4_PWM_3V3") (class "Default")
      (node (ref "U1") (pin "32") (pinfunction "PA7_32") (pintype "unspecified"))
      (node (ref "U7") (pin "3") (pinfunction "A2_3") (pintype "unspecified"))
    )
    (net (code "37") (name "BLDC4_REV") (class "Default")
      (node (ref "CN4") (pin "4") (pinfunction "4_4") (pintype "unspecified"))
      (node (ref "U7") (pin "11") (pinfunction "B3_11") (pintype "unspecified"))
    )
    (net (code "38") (name "BLDC4_REV_3V3") (class "Default")
      (node (ref "U1") (pin "30") (pinfunction "PA5_30") (pintype "unspecified"))
      (node (ref "U7") (pin "4") (pinfunction "A3_4") (pintype "unspecified"))
    )
    (net (code "39") (name "BOOT0") (class "Default")
      (node (ref "H1") (pin "1") (pinfunction "1_1") (pintype "unspecified"))
      (node (ref "R4") (pin "2") (pinfunction "2_2") (pintype "input"))
      (node (ref "U1") (pin "94") (pinfunction "BOOT0_94") (pintype "unspecified"))
    )
    (net (code "40") (name "GND") (class "Default")
      (node (ref "C1") (pin "2") (pinfunction "2_2") (pintype "input"))
      (node (ref "C10") (pin "1") (pinfunction "1_1") (pintype "input"))
      (node (ref "C11") (pin "1") (pinfunction "1_1") (pintype "input"))
      (node (ref "C12") (pin "1") (pinfunction "1_1") (pintype "input"))
      (node (ref "C13") (pin "1") (pinfunction "1_1") (pintype "input"))
      (node (ref "C14") (pin "1") (pinfunction "1_1") (pintype "input"))
      (node (ref "C15") (pin "1") (pinfunction "1_1") (pintype "input"))
      (node (ref "C16") (pin "1") (pinfunction "1_1") (pintype "input"))
      (node (ref "C17") (pin "1") (pinfunction "1_1") (pintype "input"))
      (node (ref "C18") (pin "1") (pinfunction "1_1") (pintype "input"))
      (node (ref "C19") (pin "2") (pinfunction "2_2") (pintype "input"))
      (node (ref "C2") (pin "1") (pinfunction "1_1") (pintype "input"))
      (node (ref "C20") (pin "2") (pinfunction "2_2") (pintype "input"))
      (node (ref "C21") (pin "2") (pinfunction "2_2") (pintype "input"))
      (node (ref "C22") (pin "2") (pinfunction "2_2") (pintype "input"))
      (node (ref "C24") (pin "2") (pinfunction "2_2") (pintype "input"))
      (node (ref "C25") (pin "2") (pinfunction "2_2") (pintype "input"))
      (node (ref "C26") (pin "1") (pinfunction "1_1") (pintype "unspecified"))
      (node (ref "C27") (pin "2") (pinfunction "2_2") (pintype "input"))
      (node (ref "C28") (pin "2") (pinfunction "2_2") (pintype "input"))
      (node (ref "C29") (pin "2") (pinfunction "2_2") (pintype "input"))
      (node (ref "C3") (pin "1") (pinfunction "1_1") (pintype "input"))
      (node (ref "C30") (pin "2") (pinfunction "2_2") (pintype "input"))
      (node (ref "C32") (pin "2") (pinfunction "2_2") (pintype "input"))
      (node (ref "C33") (pin "2") (pinfunction "2_2") (pintype "input"))
      (node (ref "C34") (pin "1") (pinfunction "1_1") (pintype "unspecified"))
      (node (ref "C4") (pin "1") (pinfunction "1_1") (pintype "input"))
      (node (ref "C43") (pin "1") (pinfunction "1_1") (pintype "input"))
      (node (ref "C5") (pin "1") (pinfunction "1_1") (pintype "input"))
      (node (ref "C6") (pin "1") (pinfunction "1_1") (pintype "input"))
      (node (ref "C7") (pin "1") (pinfunction "1_1") (pintype "input"))
      (node (ref "C8") (pin "1") (pinfunction "1_1") (pintype "input"))
      (node (ref "C9") (pin "1") (pinfunction "1_1") (pintype "input"))
      (node (ref "CN1") (pin "1") (pinfunction "1_1") (pintype "unspecified"))
      (node (ref "CN2") (pin "1") (pinfunction "1_1") (pintype "unspecified"))
      (node (ref "CN3") (pin "1") (pinfunction "1_1") (pintype "unspecified"))
      (node (ref "CN4") (pin "1") (pinfunction "1_1") (pintype "unspecified"))
      (node (ref "CN6") (pin "4") (pinfunction "4_4") (pintype "unspecified"))
      (node (ref "D1") (pin "1") (pinfunction "A_1") (pintype "unspecified"))
      (node (ref "D2") (pin "1") (pinfunction "A_1") (pintype "unspecified"))
      (node (ref "H1") (pin "3") (pinfunction "3_3") (pintype "unspecified"))
      (node (ref "H2") (pin "3") (pinfunction "3_3") (pintype "unspecified"))
      (node (ref "LED1") (pin "2") (pinfunction "-_2") (pintype "unspecified"))
      (node (ref "LED2") (pin "2") (pinfunction "-_2") (pintype "unspecified"))
      (node (ref "P1") (pin "1") (pinfunction "1_1") (pintype "unspecified"))
      (node (ref "Q1") (pin "2") (pinfunction "E_2") (pintype "input"))
      (node (ref "R11") (pin "1") (pinfunction "1_1") (pintype "input"))
      (node (ref "R16") (pin "2") (pinfunction "2_2") (pintype "input"))
      (node (ref "R18") (pin "2") (pinfunction "2_2") (pintype "input"))
      (node (ref "R20") (pin "2") (pinfunction "2_2") (pintype "input"))
      (node (ref "R22") (pin "2") (pinfunction "2_2") (pintype "input"))
      (node (ref "R4") (pin "1") (pinfunction "1_1") (pintype "input"))
      (node (ref "R5") (pin "1") (pinfunction "1_1") (pintype "input"))
      (node (ref "R8") (pin "1") (pinfunction "1_1") (pintype "input"))
      (node (ref "SW1") (pin "1") (pinfunction "1_1") (pintype "unspecified"))
      (node (ref "U1") (pin "10") (pinfunction "VSS_10") (pintype "unspecified"))
      (node (ref "U1") (pin "20") (pinfunction "VSSA_20") (pintype "unspecified"))
      (node (ref "U1") (pin "27") (pinfunction "VSS_27") (pintype "unspecified"))
      (node (ref "U1") (pin "74") (pinfunction "VSS_74") (pintype "unspecified"))
      (node (ref "U1") (pin "99") (pinfunction "VSS_99") (pintype "unspecified"))
      (node (ref "U12") (pin "4") (pinfunction "GND_4") (pintype "unspecified"))
      (node (ref "U13") (pin "12") (pinfunction "12_12") (pintype "unspecified"))
      (node (ref "U2") (pin "6") (pinfunction "GND_6") (pintype "unspecified"))
      (node (ref "U2") (pin "9") (pinfunction "PowerPAD_9") (pintype "unspecified"))
      (node (ref "U3") (pin "7") (pinfunction "GND_7") (pintype "unspecified"))
      (node (ref "U4") (pin "7") (pinfunction "GND_7") (pintype "unspecified"))
      (node (ref "U5") (pin "6") (pinfunction "GND_6") (pintype "unspecified"))
      (node (ref "U5") (pin "9") (pinfunction "PowerPAD_9") (pintype "unspecified"))
      (node (ref "U6") (pin "7") (pinfunction "GND_7") (pintype "unspecified"))
      (node (ref "U7") (pin "7") (pinfunction "GND_7") (pintype "unspecified"))
      (node (ref "X3") (pin "2") (pinfunction "GND_2") (pintype "unspecified"))
      (node (ref "X3") (pin "4") (pinfunction "GND_4") (pintype "unspecified"))
    )
    (net (code "41") (name "I2C1_SCL") (class "Default")
      (node (ref "U1") (pin "92") (pinfunction "PB6_92") (pintype "unspecified"))
      (node (ref "U27") (pin "2") (pinfunction "2_2") (pintype "unspecified"))
    )
    (net (code "42") (name "I2C1_SDA") (class "Default")
      (node (ref "U1") (pin "93") (pinfunction "PB7_93") (pintype "unspecified"))
      (node (ref "U27") (pin "1") (pinfunction "1_1") (pintype "unspecified"))
    )
    (net (code "43") (name "MC7RE_SBUS") (class "Default")
      (node (ref "H2") (pin "1") (pinfunction "1_1") (pintype "unspecified"))
      (node (ref "R13") (pin "2") (pinfunction "2_2") (pintype "input"))
    )
    (net (code "44") (name "Net-(D1-K)") (class "Default")
      (node (ref "C23") (pin "1") (pinfunction "1_1") (pintype "input"))
      (node (ref "D1") (pin "2") (pinfunction "K_2") (pintype "unspecified"))
      (node (ref "L1") (pin "2") (pinfunction "2_2") (pintype "unspecified"))
      (node (ref "U2") (pin "8") (pinfunction "PH_8") (pintype "unspecified"))
    )
    (net (code "45") (name "Net-(D2-K)") (class "Default")
      (node (ref "C31") (pin "1") (pinfunction "1_1") (pintype "input"))
      (node (ref "D2") (pin "2") (pinfunction "K_2") (pintype "unspecified"))
      (node (ref "L2") (pin "2") (pinfunction "2_2") (pintype "unspecified"))
      (node (ref "U5") (pin "8") (pinfunction "PH_8") (pintype "unspecified"))
    )
    (net (code "46") (name "Net-(LED1-+)") (class "Default")
      (node (ref "LED1") (pin "1") (pinfunction "+_1") (pintype "unspecified"))
      (node (ref "R2") (pin "1") (pinfunction "1_1") (pintype "input"))
    )
    (net (code "47") (name "Net-(LED2-+)") (class "Default")
      (node (ref "LED2") (pin "1") (pinfunction "+_1") (pintype "unspecified"))
      (node (ref "R14") (pin "1") (pinfunction "1_1") (pintype "input"))
    )
    (net (code "48") (name "Net-(P1-Pad2)") (class "Default")
      (node (ref "P1") (pin "2") (pinfunction "2_2") (pintype "unspecified"))
      (node (ref "U24") (pin "2") (pinfunction "2_2") (pintype "unspecified"))
    )
    (net (code "49") (name "Net-(Q1-B)") (class "Default")
      (node (ref "Q1") (pin "1") (pinfunction "B_1") (pintype "input"))
      (node (ref "R13") (pin "1") (pinfunction "1_1") (pintype "input"))
    )
    (net (code "50") (name "Net-(U1-NRST)") (class "Default")
      (node (ref "C8") (pin "2") (pinfunction "2_2") (pintype "input"))
      (node (ref "SW1") (pin "2") (pinfunction "2_2") (pintype "unspecified"))
      (node (ref "U1") (pin "14") (pinfunction "NRST_14") (pintype "unspecified"))
    )
    (net (code "51") (name "Net-(U1-PB2)") (class "Default")
      (node (ref "R5") (pin "2") (pinfunction "2_2") (pintype "input"))
      (node (ref "U1") (pin "37") (pinfunction "PB2_37") (pintype "unspecified"))
    )
    (net (code "52") (name "Net-(U1-PC14)") (class "Default")
      (node (ref "C7") (pin "2") (pinfunction "2_2") (pintype "input"))
      (node (ref "U1") (pin "8") (pinfunction "PC14_8") (pintype "unspecified"))
      (node (ref "X2") (pin "2") (pinfunction "2_2") (pintype "unspecified"))
    )
    (net (code "53") (name "Net-(U1-PC15)") (class "Default")
      (node (ref "C9") (pin "2") (pinfunction "2_2") (pintype "input"))
      (node (ref "U1") (pin "9") (pinfunction "PC15_9") (pintype "unspecified"))
      (node (ref "X2") (pin "1") (pinfunction "1_1") (pintype "unspecified"))
    )
    (net (code "54") (name "Net-(U1-PH0)") (class "Default")
      (node (ref "C2") (pin "2") (pinfunction "2_2") (pintype "input"))
      (node (ref "U1") (pin "12") (pinfunction "PH0_12") (pintype "unspecified"))
      (node (ref "X3") (pin "3") (pinfunction "OSC2_3") (pintype "unspecified"))
    )
    (net (code "55") (name "Net-(U1-PH1)") (class "Default")
      (node (ref "C3") (pin "2") (pinfunction "2_2") (pintype "input"))
      (node (ref "U1") (pin "13") (pinfunction "PH1_13") (pintype "unspecified"))
      (node (ref "X3") (pin "1") (pinfunction "OSC1_1") (pintype "unspecified"))
    )
    (net (code "56") (name "Net-(U1-VCAP_1)") (class "Default")
      (node (ref "C5") (pin "2") (pinfunction "2_2") (pintype "input"))
      (node (ref "U1") (pin "49") (pinfunction "VCAP_1_49") (pintype "unspecified"))
    )
    (net (code "57") (name "Net-(U1-VCAP_2)") (class "Default")
      (node (ref "C6") (pin "2") (pinfunction "2_2") (pintype "input"))
      (node (ref "U1") (pin "73") (pinfunction "VCAP_2_73") (pintype "unspecified"))
    )
    (net (code "58") (name "Net-(U1-VREF+)") (class "Default")
      (node (ref "R3") (pin "1") (pinfunction "1_1") (pintype "input"))
      (node (ref "U1") (pin "21") (pinfunction "VREF+_21") (pintype "unspecified"))
    )
    (net (code "59") (name "Net-(U2-BOOT)") (class "Default")
      (node (ref "C23") (pin "2") (pinfunction "2_2") (pintype "input"))
      (node (ref "U2") (pin "1") (pinfunction "BOOT_1") (pintype "unspecified"))
    )
    (net (code "60") (name "Net-(U5-BOOT)") (class "Default")
      (node (ref "C31") (pin "2") (pinfunction "2_2") (pintype "input"))
      (node (ref "U5") (pin "1") (pinfunction "BOOT_1") (pintype "unspecified"))
    )
    (net (code "61") (name "PUMP_IN1") (class "Default")
      (node (ref "CN6") (pin "2") (pinfunction "2_2") (pintype "unspecified"))
      (node (ref "U1") (pin "96") (pinfunction "PB9_96") (pintype "unspecified"))
    )
    (net (code "62") (name "PUMP_IN2") (class "Default")
      (node (ref "CN6") (pin "1") (pinfunction "1_1") (pintype "unspecified"))
      (node (ref "U1") (pin "95") (pinfunction "PB8_95") (pintype "unspecified"))
    )
    (net (code "63") (name "PUMP_VREF") (class "Default")
      (node (ref "CN6") (pin "3") (pinfunction "3_3") (pintype "unspecified"))
      (node (ref "U1") (pin "97") (pinfunction "PE0_97") (pintype "unspecified"))
    )
    (net (code "64") (name "REMOTE_DATA") (class "Default")
      (node (ref "Q1") (pin "3") (pinfunction "C_3") (pintype "input"))
      (node (ref "R12") (pin "1") (pinfunction "1_1") (pintype "input"))
      (node (ref "U1") (pin "87") (pinfunction "PD6_87") (pintype "unspecified"))
    )
    (net (code "65") (name "SPI3_CS") (class "Default")
      (node (ref "U1") (pin "77") (pinfunction "PA15_77") (pintype "unspecified"))
      (node (ref "U12") (pin "1") (pinfunction "CS#_1") (pintype "unspecified"))
    )
    (net (code "66") (name "SPI3_MISO") (class "Default")
      (node (ref "U1") (pin "79") (pinfunction "PC11_79") (pintype "unspecified"))
      (node (ref "U12") (pin "2") (pinfunction "DO/IO1_2") (pintype "unspecified"))
    )
    (net (code "67") (name "SPI3_MOSI") (class "Default")
      (node (ref "U1") (pin "91") (pinfunction "PB5_91") (pintype "unspecified"))
      (node (ref "U12") (pin "5") (pinfunction "DI/IO0_5") (pintype "unspecified"))
    )
    (net (code "68") (name "SPI3_SCK") (class "Default")
      (node (ref "U1") (pin "78") (pinfunction "PC10_78") (pintype "unspecified"))
      (node (ref "U12") (pin "6") (pinfunction "CLK_6") (pintype "unspecified"))
    )
    (net (code "69") (name "STEPPER_DECAY") (class "Default")
      (node (ref "U1") (pin "57") (pinfunction "PD10_57") (pintype "unspecified"))
      (node (ref "U13") (pin "8") (pinfunction "8_8") (pintype "unspecified"))
    )
    (net (code "70") (name "STEPPER_DIR") (class "Default")
      (node (ref "U1") (pin "56") (pinfunction "PD9_56") (pintype "unspecified"))
      (node (ref "U13") (pin "7") (pinfunction "7_7") (pintype "unspecified"))
    )
    (net (code "71") (name "STEPPER_MODE0") (class "Default")
      (node (ref "U1") (pin "53") (pinfunction "PB14_53") (pintype "unspecified"))
      (node (ref "U13") (pin "4") (pinfunction "4_4") (pintype "unspecified"))
    )
    (net (code "72") (name "STEPPER_MODE1") (class "Default")
      (node (ref "U1") (pin "52") (pinfunction "PB13_52") (pintype "unspecified"))
      (node (ref "U13") (pin "3") (pinfunction "3_3") (pintype "unspecified"))
    )
    (net (code "73") (name "STEPPER_MODE2") (class "Default")
      (node (ref "U1") (pin "51") (pinfunction "PB12_51") (pintype "unspecified"))
      (node (ref "U13") (pin "2") (pinfunction "2_2") (pintype "unspecified"))
    )
    (net (code "74") (name "STEPPER_NENBL") (class "Default")
      (node (ref "U1") (pin "55") (pinfunction "PD8_55") (pintype "unspecified"))
      (node (ref "U13") (pin "6") (pinfunction "6_6") (pintype "unspecified"))
    )
    (net (code "75") (name "STEPPER_NFLT") (class "Default")
      (node (ref "U1") (pin "63") (pinfunction "PC6_63") (pintype "unspecified"))
      (node (ref "U13") (pin "9") (pinfunction "9_9") (pintype "unspecified"))
    )
    (net (code "76") (name "STEPPER_NHOME") (class "Default")
      (node (ref "U1") (pin "46") (pinfunction "PE15_46") (pintype "unspecified"))
      (node (ref "U13") (pin "1") (pinfunction "1_1") (pintype "unspecified"))
    )
    (net (code "77") (name "STEPPER_NRST") (class "Default")
      (node (ref "U1") (pin "65") (pinfunction "PC8_65") (pintype "unspecified"))
      (node (ref "U13") (pin "11") (pinfunction "11_11") (pintype "unspecified"))
    )
    (net (code "78") (name "STEPPER_NSLP") (class "Default")
      (node (ref "U1") (pin "64") (pinfunction "PC7_64") (pintype "unspecified"))
      (node (ref "U13") (pin "10") (pinfunction "10_10") (pintype "unspecified"))
    )
    (net (code "79") (name "STEPPER_STEP") (class "Default")
      (node (ref "U1") (pin "54") (pinfunction "PB15_54") (pintype "unspecified"))
      (node (ref "U13") (pin "5") (pinfunction "5_5") (pintype "unspecified"))
    )
    (net (code "80") (name "SWCLK") (class "Default")
      (node (ref "H1") (pin "5") (pinfunction "5_5") (pintype "unspecified"))
      (node (ref "U1") (pin "76") (pinfunction "PA14_76") (pintype "unspecified"))
    )
    (net (code "81") (name "SWDIO") (class "Default")
      (node (ref "H1") (pin "4") (pinfunction "4_4") (pintype "unspecified"))
      (node (ref "U1") (pin "72") (pinfunction "PA13_72") (pintype "unspecified"))
    )
    (net (code "82") (name "UART5_RX") (class "Default")
      (node (ref "U1") (pin "83") (pinfunction "PD2_83") (pintype "unspecified"))
      (node (ref "U28") (pin "2") (pinfunction "2_2") (pintype "unspecified"))
    )
    (net (code "83") (name "UART5_TX") (class "Default")
      (node (ref "U1") (pin "80") (pinfunction "PC12_80") (pintype "unspecified"))
      (node (ref "U28") (pin "1") (pinfunction "1_1") (pintype "unspecified"))
    )
    (net (code "84") (name "USART1_RX") (class "Default")
      (node (ref "U1") (pin "69") (pinfunction "PA10_69") (pintype "unspecified"))
      (node (ref "U26") (pin "2") (pinfunction "2_2") (pintype "unspecified"))
    )
    (net (code "85") (name "USART1_TX") (class "Default")
      (node (ref "U1") (pin "68") (pinfunction "PA9_68") (pintype "unspecified"))
      (node (ref "U26") (pin "1") (pinfunction "1_1") (pintype "unspecified"))
    )
    (net (code "86") (name "VDDA") (class "Default")
      (node (ref "C1") (pin "1") (pinfunction "1_1") (pintype "input"))
      (node (ref "C18") (pin "2") (pinfunction "2_2") (pintype "input"))
      (node (ref "R1") (pin "2") (pinfunction "2_2") (pintype "input"))
      (node (ref "R3") (pin "2") (pinfunction "2_2") (pintype "input"))
      (node (ref "U1") (pin "22") (pinfunction "VDDA_22") (pintype "unspecified"))
    )
    (net (code "87") (name "VIN_24V") (class "Default")
      (node (ref "C25") (pin "1") (pinfunction "1_1") (pintype "input"))
      (node (ref "C26") (pin "2") (pinfunction "2_2") (pintype "unspecified"))
      (node (ref "C33") (pin "1") (pinfunction "1_1") (pintype "input"))
      (node (ref "C34") (pin "2") (pinfunction "2_2") (pintype "unspecified"))
      (node (ref "U2") (pin "7") (pinfunction "VIN_7") (pintype "unspecified"))
      (node (ref "U24") (pin "3") (pinfunction "3_3") (pintype "unspecified"))
      (node (ref "U5") (pin "7") (pinfunction "VIN_7") (pintype "unspecified"))
    )
    (net (code "88") (name "VSEN_3V3") (class "Default")
      (node (ref "R6") (pin "1") (pinfunction "1_1") (pintype "input"))
      (node (ref "R8") (pin "2") (pinfunction "2_2") (pintype "input"))
      (node (ref "U2") (pin "4") (pinfunction "VSENSE_4") (pintype "unspecified"))
    )
    (net (code "89") (name "VSEN_5V") (class "Default")
      (node (ref "R11") (pin "2") (pinfunction "2_2") (pintype "input"))
      (node (ref "R9") (pin "1") (pinfunction "1_1") (pintype "input"))
      (node (ref "U5") (pin "4") (pinfunction "VSENSE_4") (pintype "unspecified"))
    )
    (net (code "90") (name "unconnected-(U1-PA1-Pad24)") (class "Default")
      (node (ref "U1") (pin "24") (pinfunction "PA1_24") (pintype "unspecified"))
    )
    (net (code "91") (name "unconnected-(U1-PA2-Pad25)") (class "Default")
      (node (ref "U1") (pin "25") (pinfunction "PA2_25") (pintype "unspecified"))
    )
    (net (code "92") (name "unconnected-(U1-PA3-Pad26)") (class "Default")
      (node (ref "U1") (pin "26") (pinfunction "PA3_26") (pintype "unspecified"))
    )
    (net (code "93") (name "unconnected-(U1-PA8-Pad67)") (class "Default")
      (node (ref "U1") (pin "67") (pinfunction "PA8_67") (pintype "unspecified"))
    )
    (net (code "94") (name "unconnected-(U1-PA11-Pad70)") (class "Default")
      (node (ref "U1") (pin "70") (pinfunction "PA11_70") (pintype "unspecified"))
    )
    (net (code "95") (name "unconnected-(U1-PA12-Pad71)") (class "Default")
      (node (ref "U1") (pin "71") (pinfunction "PA12_71") (pintype "unspecified"))
    )
    (net (code "96") (name "unconnected-(U1-PB3-Pad89)") (class "Default")
      (node (ref "U1") (pin "89") (pinfunction "PB3_89") (pintype "unspecified"))
    )
    (net (code "97") (name "unconnected-(U1-PB4-Pad90)") (class "Default")
      (node (ref "U1") (pin "90") (pinfunction "PB4_90") (pintype "unspecified"))
    )
    (net (code "98") (name "unconnected-(U1-PB10-Pad47)") (class "Default")
      (node (ref "U1") (pin "47") (pinfunction "PB10_47") (pintype "unspecified"))
    )
    (net (code "99") (name "unconnected-(U1-PB11-Pad48)") (class "Default")
      (node (ref "U1") (pin "48") (pinfunction "PB11_48") (pintype "unspecified"))
    )
    (net (code "100") (name "unconnected-(U1-PC4-Pad33)") (class "Default")
      (node (ref "U1") (pin "33") (pinfunction "PC4_33") (pintype "unspecified"))
    )
    (net (code "101") (name "unconnected-(U1-PC5-Pad34)") (class "Default")
      (node (ref "U1") (pin "34") (pinfunction "PC5_34") (pintype "unspecified"))
    )
    (net (code "102") (name "unconnected-(U1-PC9-Pad66)") (class "Default")
      (node (ref "U1") (pin "66") (pinfunction "PC9_66") (pintype "unspecified"))
    )
    (net (code "103") (name "unconnected-(U1-PD0-Pad81)") (class "Default")
      (node (ref "U1") (pin "81") (pinfunction "PD0_81") (pintype "unspecified"))
    )
    (net (code "104") (name "unconnected-(U1-PD1-Pad82)") (class "Default")
      (node (ref "U1") (pin "82") (pinfunction "PD1_82") (pintype "unspecified"))
    )
    (net (code "105") (name "unconnected-(U1-PD3-Pad84)") (class "Default")
      (node (ref "U1") (pin "84") (pinfunction "PD3_84") (pintype "unspecified"))
    )
    (net (code "106") (name "unconnected-(U1-PD4-Pad85)") (class "Default")
      (node (ref "U1") (pin "85") (pinfunction "PD4_85") (pintype "unspecified"))
    )
    (net (code "107") (name "unconnected-(U1-PD5-Pad86)") (class "Default")
      (node (ref "U1") (pin "86") (pinfunction "PD5_86") (pintype "unspecified"))
    )
    (net (code "108") (name "unconnected-(U1-PD7-Pad88)") (class "Default")
      (node (ref "U1") (pin "88") (pinfunction "PD7_88") (pintype "unspecified"))
    )
    (net (code "109") (name "unconnected-(U1-PD11-Pad58)") (class "Default")
      (node (ref "U1") (pin "58") (pinfunction "PD11_58") (pintype "unspecified"))
    )
    (net (code "110") (name "unconnected-(U1-PD12-Pad59)") (class "Default")
      (node (ref "U1") (pin "59") (pinfunction "PD12_59") (pintype "unspecified"))
    )
    (net (code "111") (name "unconnected-(U1-PD13-Pad60)") (class "Default")
      (node (ref "U1") (pin "60") (pinfunction "PD13_60") (pintype "unspecified"))
    )
    (net (code "112") (name "unconnected-(U1-PD14-Pad61)") (class "Default")
      (node (ref "U1") (pin "61") (pinfunction "PD14_61") (pintype "unspecified"))
    )
    (net (code "113") (name "unconnected-(U1-PD15-Pad62)") (class "Default")
      (node (ref "U1") (pin "62") (pinfunction "PD15_62") (pintype "unspecified"))
    )
    (net (code "114") (name "unconnected-(U1-PE1-Pad98)") (class "Default")
      (node (ref "U1") (pin "98") (pinfunction "PE1_98") (pintype "unspecified"))
    )
    (net (code "115") (name "unconnected-(U1-PE2-Pad1)") (class "Default")
      (node (ref "U1") (pin "1") (pinfunction "PE2_1") (pintype "unspecified"))
    )
    (net (code "116") (name "unconnected-(U1-PE3-Pad2)") (class "Default")
      (node (ref "U1") (pin "2") (pinfunction "PE3_2") (pintype "unspecified"))
    )
    (net (code "117") (name "unconnected-(U1-PE4-Pad3)") (class "Default")
      (node (ref "U1") (pin "3") (pinfunction "PE4_3") (pintype "unspecified"))
    )
    (net (code "118") (name "unconnected-(U1-PE8-Pad39)") (class "Default")
      (node (ref "U1") (pin "39") (pinfunction "PE8_39") (pintype "unspecified"))
    )
    (net (code "119") (name "unconnected-(U1-PE10-Pad41)") (class "Default")
      (node (ref "U1") (pin "41") (pinfunction "PE10_41") (pintype "unspecified"))
    )
    (net (code "120") (name "unconnected-(U1-PE11-Pad42)") (class "Default")
      (node (ref "U1") (pin "42") (pinfunction "PE11_42") (pintype "unspecified"))
    )
    (net (code "121") (name "unconnected-(U1-PE12-Pad43)") (class "Default")
      (node (ref "U1") (pin "43") (pinfunction "PE12_43") (pintype "unspecified"))
    )
    (net (code "122") (name "unconnected-(U1-PE13-Pad44)") (class "Default")
      (node (ref "U1") (pin "44") (pinfunction "PE13_44") (pintype "unspecified"))
    )
    (net (code "123") (name "unconnected-(U1-PE14-Pad45)") (class "Default")
      (node (ref "U1") (pin "45") (pinfunction "PE14_45") (pintype "unspecified"))
    )
    (net (code "124") (name "unconnected-(U2-ENA-Pad5)") (class "Default")
      (node (ref "U2") (pin "5") (pinfunction "ENA_5") (pintype "unspecified+no_connect"))
    )
    (net (code "125") (name "unconnected-(U2-NC-Pad2)") (class "Default")
      (node (ref "U2") (pin "2") (pinfunction "NC_2") (pintype "unspecified+no_connect"))
    )
    (net (code "126") (name "unconnected-(U2-NC-Pad3)") (class "Default")
      (node (ref "U2") (pin "3") (pinfunction "NC_3") (pintype "unspecified+no_connect"))
    )
    (net (code "127") (name "unconnected-(U3-A3-Pad4)") (class "Default")
      (node (ref "U3") (pin "4") (pinfunction "A3_4") (pintype "unspecified"))
    )
    (net (code "128") (name "unconnected-(U3-B3-Pad11)") (class "Default")
      (node (ref "U3") (pin "11") (pinfunction "B3_11") (pintype "unspecified"))
    )
    (net (code "129") (name "unconnected-(U3-NC-Pad6)") (class "Default")
      (node (ref "U3") (pin "6") (pinfunction "NC_6") (pintype "unspecified"))
    )
    (net (code "130") (name "unconnected-(U3-NC-Pad9)") (class "Default")
      (node (ref "U3") (pin "9") (pinfunction "NC_9") (pintype "unspecified"))
    )
    (net (code "131") (name "unconnected-(U4-A1-Pad2)") (class "Default")
      (node (ref "U4") (pin "2") (pinfunction "A1_2") (pintype "unspecified"))
    )
    (net (code "132") (name "unconnected-(U4-B1-Pad13)") (class "Default")
      (node (ref "U4") (pin "13") (pinfunction "B1_13") (pintype "unspecified"))
    )
    (net (code "133") (name "unconnected-(U4-NC-Pad6)") (class "Default")
      (node (ref "U4") (pin "6") (pinfunction "NC_6") (pintype "unspecified"))
    )
    (net (code "134") (name "unconnected-(U4-NC-Pad9)") (class "Default")
      (node (ref "U4") (pin "9") (pinfunction "NC_9") (pintype "unspecified"))
    )
    (net (code "135") (name "unconnected-(U5-ENA-Pad5)") (class "Default")
      (node (ref "U5") (pin "5") (pinfunction "ENA_5") (pintype "unspecified+no_connect"))
    )
    (net (code "136") (name "unconnected-(U5-NC-Pad2)") (class "Default")
      (node (ref "U5") (pin "2") (pinfunction "NC_2") (pintype "unspecified+no_connect"))
    )
    (net (code "137") (name "unconnected-(U5-NC-Pad3)") (class "Default")
      (node (ref "U5") (pin "3") (pinfunction "NC_3") (pintype "unspecified+no_connect"))
    )
    (net (code "138") (name "unconnected-(U6-A1-Pad2)") (class "Default")
      (node (ref "U6") (pin "2") (pinfunction "A1_2") (pintype "unspecified"))
    )
    (net (code "139") (name "unconnected-(U6-B1-Pad13)") (class "Default")
      (node (ref "U6") (pin "13") (pinfunction "B1_13") (pintype "unspecified"))
    )
    (net (code "140") (name "unconnected-(U6-NC-Pad6)") (class "Default")
      (node (ref "U6") (pin "6") (pinfunction "NC_6") (pintype "unspecified"))
    )
    (net (code "141") (name "unconnected-(U6-NC-Pad9)") (class "Default")
      (node (ref "U6") (pin "9") (pinfunction "NC_9") (pintype "unspecified"))
    )
    (net (code "142") (name "unconnected-(U7-A1-Pad2)") (class "Default")
      (node (ref "U7") (pin "2") (pinfunction "A1_2") (pintype "unspecified"))
    )
    (net (code "143") (name "unconnected-(U7-B1-Pad13)") (class "Default")
      (node (ref "U7") (pin "13") (pinfunction "B1_13") (pintype "unspecified"))
    )
    (net (code "144") (name "unconnected-(U7-NC-Pad6)") (class "Default")
      (node (ref "U7") (pin "6") (pinfunction "NC_6") (pintype "unspecified"))
    )
    (net (code "145") (name "unconnected-(U7-NC-Pad9)") (class "Default")
      (node (ref "U7") (pin "9") (pinfunction "NC_9") (pintype "unspecified"))
    )
    (net (code "146") (name "unconnected-(U24-Pad1)") (class "Default")
      (node (ref "U24") (pin "1") (pinfunction "1_1") (pintype "unspecified+no_connect"))
    )
  )
)
